# RS232_2xNPN_6Pin_New.net
KiCad netlist of a schematic drawn in EAGLE
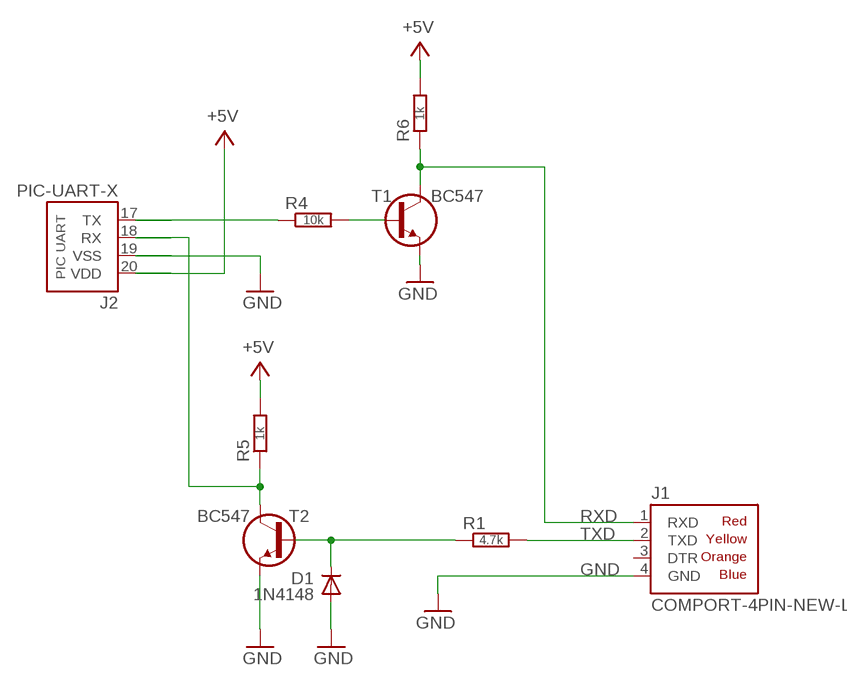
[diagram p0: schematic, sheet 1]

(export (version "E")
  (design (tool "Eeschema 10.0.6"))
  (components
    (comp (ref "D1")
      (value "1N4148")
      (footprint "eagle-import:DO34-5")
      (libsource (lib "eagle-import") (part "1N414834-5"))
    )
    (comp (ref "J1")
      (value "COMPORT-4PIN-NEW-L")
      (footprint "eagle-import:RS232-4PIN-NEW-L")
      (libsource (lib "eagle-import") (part "COMPORT-4PIN-NEW-L"))
    )
    (comp (ref "J2")
      (value "PIC-UART-X")
      (footprint "eagle-import:PIC-UART-X")
      (libsource (lib "eagle-import") (part "PIC-UART-X"))
    )
    (comp (ref "R1")
      (value "4.7k")
      (footprint "eagle-import:0202_10")
      (libsource (lib "eagle-import") (part "R0202/10"))
    )
    (comp (ref "R4")
      (value "10k")
      (footprint "eagle-import:0202_7")
      (libsource (lib "eagle-import") (part "R0202/7"))
    )
    (comp (ref "R5")
      (value "1k")
      (footprint "eagle-import:0202_5-V")
      (libsource (lib "eagle-import") (part "R0202/5-V"))
    )
    (comp (ref "R6")
      (value "1k")
      (footprint "eagle-import:0202_7")
      (libsource (lib "eagle-import") (part "R0202/7"))
    )
    (comp (ref "T1")
      (value "BC547")
      (footprint "eagle-import:TO92-CBE")
      (libsource (lib "eagle-import") (part "BC547CBE"))
    )
    (comp (ref "T2")
      (value "BC547")
      (footprint "eagle-import:TO92-CBE")
      (libsource (lib "eagle-import") (part "BC547CBE"))
    )
  )
  (nets
    (net (code "1") (name "+5V") (class "Default")
      (node (ref "J2") (pin "20") (pinfunction "VDD_20") (pintype "passive"))
      (node (ref "R5") (pin "2") (pinfunction "2_2") (pintype "passive"))
      (node (ref "R6") (pin "2") (pinfunction "2_2") (pintype "passive"))
    )
    (net (code "2") (name "/RXD") (class "Default")
      (node (ref "J1") (pin "1") (pinfunction "RXD_1") (pintype "passive"))
      (node (ref "R6") (pin "1") (pinfunction "1_1") (pintype "passive"))
      (node (ref "T1") (pin "C") (pinfunction "C_C") (pintype "passive"))
    )
    (net (code "3") (name "/TXD") (class "Default")
      (node (ref "J1") (pin "2") (pinfunction "TXD_2") (pintype "passive"))
      (node (ref "R1") (pin "2") (pinfunction "2_2") (pintype "passive"))
    )
    (net (code "4") (name "GND") (class "Default")
      (node (ref "D1") (pin "A") (pinfunction "A_A") (pintype "passive"))
      (node (ref "J1") (pin "4") (pinfunction "GND_4") (pintype "passive"))
      (node (ref "J2") (pin "19") (pinfunction "VSS_19") (pintype "passive"))
      (node (ref "T1") (pin "E") (pinfunction "E_E") (pintype "passive"))
      (node (ref "T2") (pin "E") (pinfunction "E_E") (pintype "passive"))
    )
    (net (code "5") (name "Net-(D1-PadC)") (class "Default")
      (node (ref "D1") (pin "C") (pinfunction "C_C") (pintype "passive"))
      (node (ref "R1") (pin "1") (pinfunction "1_1") (pintype "passive"))
      (node (ref "T2") (pin "B") (pinfunction "B_B") (pintype "passive"))
    )
    (net (code "6") (name "Net-(J2-RX)") (class "Default")
      (node (ref "J2") (pin "18") (pinfunction "RX_18") (pintype "passive"))
      (node (ref "R5") (pin "1") (pinfunction "1_1") (pintype "passive"))
      (node (ref "T2") (pin "C") (pinfunction "C_C") (pintype "passive"))
    )
    (net (code "7") (name "Net-(J2-TX)") (class "Default")
      (node (ref "J2") (pin "17") (pinfunction "TX_17") (pintype "passive"))
      (node (ref "R4") (pin "1") (pinfunction "1_1") (pintype "passive"))
    )
    (net (code "8") (name "Net-(R4-Pad2)") (class "Default")
      (node (ref "R4") (pin "2") (pinfunction "2_2") (pintype "passive"))
      (node (ref "T1") (pin "B") (pinfunction "B_B") (pintype "passive"))
    )
    (net (code "9") (name "unconnected-(J1-DTR-Pad3)") (class "Default")
      (node (ref "J1") (pin "3") (pinfunction "DTR_3") (pintype "passive"))
    )
  )
)
